# SCH_01_Power.net
KiCad netlist of a schematic drawn in Altium Designer
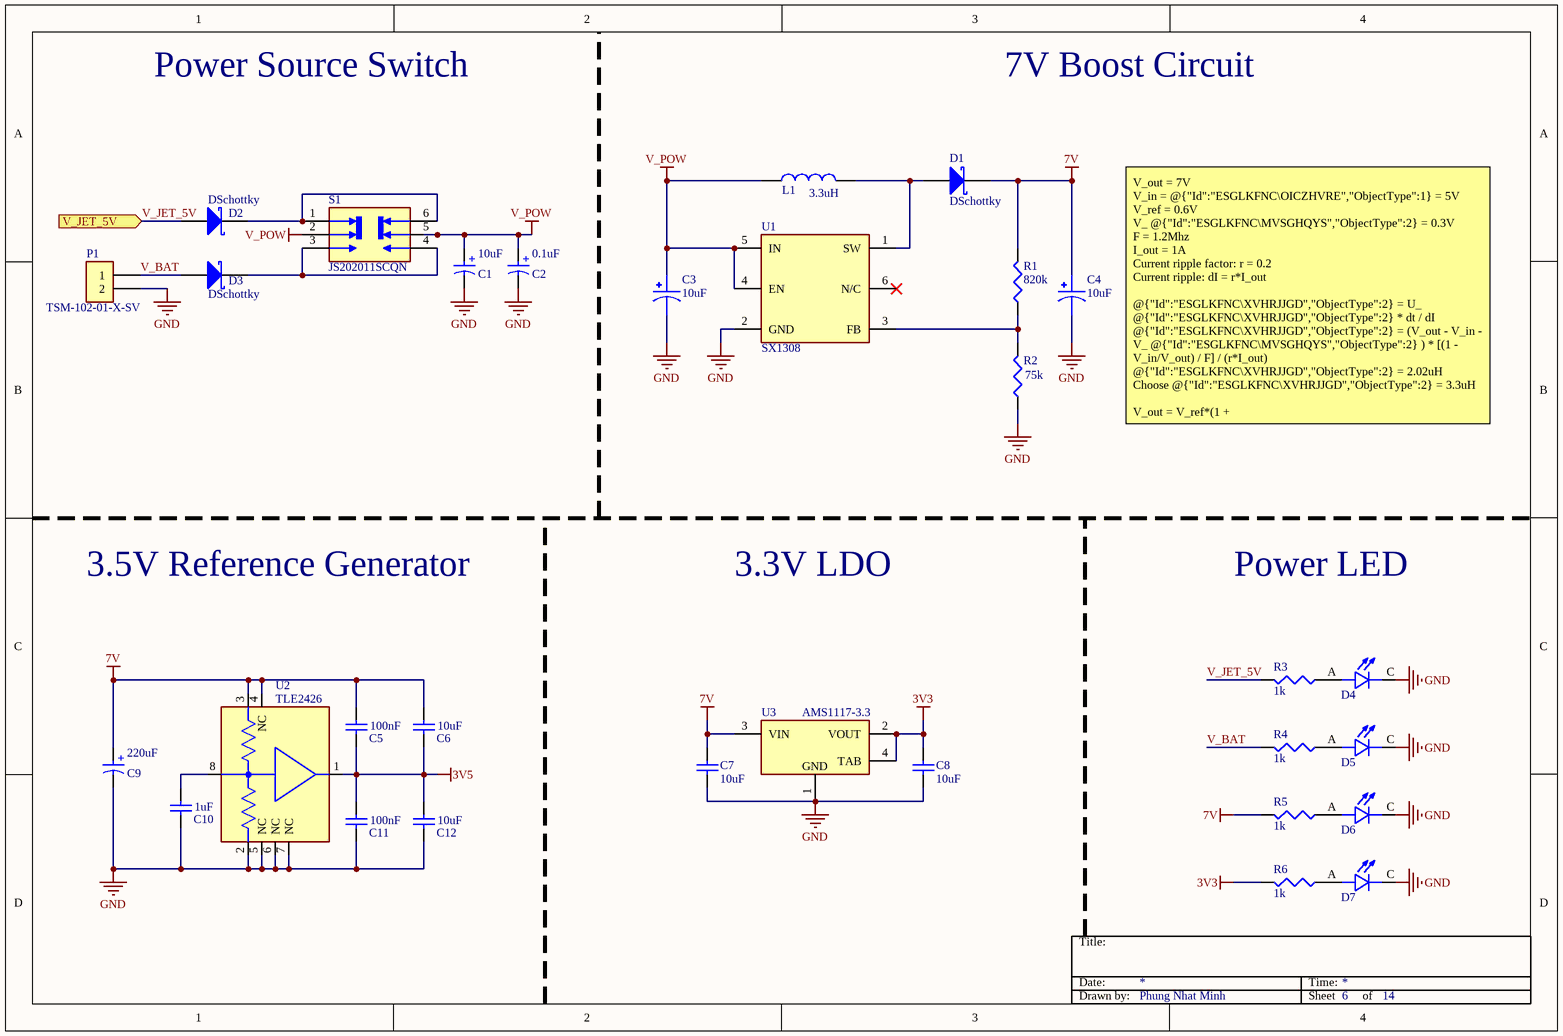
[diagram p0: SCH_01_Power.SchDoc]

(export (version "E")
  (design (tool "Eeschema 10.0.6"))
  (components
    (comp (ref "C1")
      (value "10uF")
      (footprint "WCAP-ASLI_D4H5.5")
      (description "WCAP-ASLI Aluminum Electrolytic Capacitor, V-Chip, D4 x H5.5mm, 10uF, 25V")
      (fields
        (field (name "MANUFACTURER PART NUMBER") "865080440002")
        (field (name "MANUFACTURER") "Wurth Elektronik")
      )
      (libsource (lib "Altium_WCAP-ASLI (rev22d)") (part "865080440002"))
    )
    (comp (ref "C2")
      (value "0.1uF")
      (footprint "WCAP-ASLI_D4H5.5")
      (description "WCAP-ASLI Aluminum Electrolytic Capacitor, V-Chip, D4 x H5.5mm, 0.1uF, 63V")
      (fields
        (field (name "MANUFACTURER PART NUMBER") "865080740002")
        (field (name "MANUFACTURER") "Wurth Elektronik")
      )
      (libsource (lib "Altium_WCAP-ASLI (rev22d)") (part "865080740002"))
    )
    (comp (ref "C3")
      (value "10uF")
      (footprint "CAPPM6032X280N")
      (description "10µF Molded Tantalum Capacitors 16V 2312 (6032 Metric) 2Ohm")
      (fields (field (name "MP") "TAJC106K016RNJ") (field (name "MF") "AVX Interconnect / Elco"))
      (libsource (lib "TAJC106K016RNJ") (part "TAJC106K016RNJ"))
    )
    (comp (ref "C4")
      (value "10uF")
      (footprint "CAPPM6032X280N")
      (description "10µF Molded Tantalum Capacitors 16V 2312 (6032 Metric) 2Ohm")
      (fields (field (name "MP") "TAJC106K016RNJ") (field (name "MF") "AVX Interconnect / Elco"))
      (libsource (lib "TAJC106K016RNJ") (part "TAJC106K016RNJ"))
    )
    (comp (ref "C5")
      (value "100nF")
      (footprint "WCAP-CSGP_0603_L1.6W0.8H0.8_Reflow")
      (description "WCAP-CSGP Multilayer Ceramic Chip Capacitor, General Purpose, size 0603, X7R, 100nF, 50VDC")
      (fields
        (field (name "MANUFACTURER PART NUMBER") "885012206095")
        (field (name "MANUFACTURER") "Wurth Elektronik")
      )
      (libsource (lib "Altium_WCAP-CSGP (rev24b)") (part "885012206095"))
    )
    (comp (ref "C6")
      (value "10uF")
      (footprint "WCAP-CSGP_0603_L1.6W0.8H0.8_Reflow")
      (description "WCAP-CSGP Multilayer Ceramic Chip Capacitor, General Purpose, size 0603, X5R, 10uF, 25VDC")
      (fields
        (field (name "MANUFACTURER PART NUMBER") "885012106031")
        (field (name "MANUFACTURER") "Wurth Elektronik")
      )
      (libsource (lib "Altium_WCAP-CSGP (rev24b)") (part "885012106031"))
    )
    (comp (ref "C7")
      (value "10uF")
      (footprint "WCAP-CSGP_0603_L1.6W0.8H0.8_Reflow")
      (description "WCAP-CSGP Multilayer Ceramic Chip Capacitor, General Purpose, size 0603, X5R, 10uF, 25VDC")
      (fields
        (field (name "MANUFACTURER PART NUMBER") "885012106031")
        (field (name "MANUFACTURER") "Wurth Elektronik")
      )
      (libsource (lib "Altium_WCAP-CSGP (rev24b)") (part "885012106031"))
    )
    (comp (ref "C8")
      (value "10uF")
      (footprint "WCAP-CSGP_0603_L1.6W0.8H0.8_Reflow")
      (description "WCAP-CSGP Multilayer Ceramic Chip Capacitor, General Purpose, size 0603, X5R, 10uF, 25VDC")
      (fields
        (field (name "MANUFACTURER PART NUMBER") "885012106031")
        (field (name "MANUFACTURER") "Wurth Elektronik")
      )
      (libsource (lib "Altium_WCAP-CSGP (rev24b)") (part "885012106031"))
    )
    (comp (ref "C9")
      (value "220uF")
      (footprint "WCAP-ASLI_D6.3H7.7")
      (description "WCAP-ASLI Aluminum Electrolytic Capacitor, V-Chip, D6.3 x H7.7mm, 220uF, 10V")
      (fields
        (field (name "MANUFACTURER PART NUMBER") "865080245009")
        (field (name "MANUFACTURER") "Wurth Elektronik")
      )
      (libsource (lib "Altium_WCAP-ASLI (rev22d)") (part "865080245009"))
    )
    (comp (ref "C10")
      (value "1uF")
      (footprint "WCAP-CSGP_0603_L1.6W0.8H0.8_Reflow")
      (description "WCAP-CSGP Multilayer Ceramic Chip Capacitor, General Purpose, size 0603, X7R, 1uF, 50VDC")
      (fields
        (field (name "MANUFACTURER PART NUMBER") "885012206126")
        (field (name "MANUFACTURER") "Wurth Elektronik")
      )
      (libsource (lib "Altium_WCAP-CSGP (rev24b)") (part "885012206126"))
    )
    (comp (ref "C11")
      (value "100nF")
      (footprint "WCAP-CSGP_0603_L1.6W0.8H0.8_Reflow")
      (description "WCAP-CSGP Multilayer Ceramic Chip Capacitor, General Purpose, size 0603, X7R, 100nF, 50VDC")
      (fields
        (field (name "MANUFACTURER PART NUMBER") "885012206095")
        (field (name "MANUFACTURER") "Wurth Elektronik")
      )
      (libsource (lib "Altium_WCAP-CSGP (rev24b)") (part "885012206095"))
    )
    (comp (ref "C12")
      (value "10uF")
      (footprint "WCAP-CSGP_0603_L1.6W0.8H0.8_Reflow")
      (description "WCAP-CSGP Multilayer Ceramic Chip Capacitor, General Purpose, size 0603, X5R, 10uF, 25VDC")
      (fields
        (field (name "MANUFACTURER PART NUMBER") "885012106031")
        (field (name "MANUFACTURER") "Wurth Elektronik")
      )
      (libsource (lib "Altium_WCAP-CSGP (rev24b)") (part "885012106031"))
    )
    (comp (ref "D1")
      (value "DSchottky")
      (footprint "PCBComponent_1")
      (libsource (lib "Diode_Schottky_SMA") (part "DSchottky"))
    )
    (comp (ref "D2")
      (value "DSchottky")
      (footprint "PCBComponent_1")
      (libsource (lib "Diode_Schottky_SMA") (part "DSchottky"))
    )
    (comp (ref "D3")
      (value "DSchottky")
      (footprint "PCBComponent_1")
      (libsource (lib "Diode_Schottky_SMA") (part "DSchottky"))
    )
    (comp (ref "D4")
      (value "SML-LXT0805IW-TR")
      (footprint "LEDC2012X120N")
      (fields (field (name "MF") "Lumex Opto/Components"))
      (libsource (lib "SML-LXT0805IW-TR") (part "SML-LXT0805IW-TR"))
    )
    (comp (ref "D5")
      (value "SML-LXT0805IW-TR")
      (footprint "LEDC2012X120N")
      (fields (field (name "MF") "Lumex Opto/Components"))
      (libsource (lib "SML-LXT0805IW-TR") (part "SML-LXT0805IW-TR"))
    )
    (comp (ref "D6")
      (value "SML-LXT0805IW-TR")
      (footprint "LEDC2012X120N")
      (fields (field (name "MF") "Lumex Opto/Components"))
      (libsource (lib "SML-LXT0805IW-TR") (part "SML-LXT0805IW-TR"))
    )
    (comp (ref "D7")
      (value "SML-LXT0805IW-TR")
      (footprint "LEDC2012X120N")
      (fields (field (name "MF") "Lumex Opto/Components"))
      (libsource (lib "SML-LXT0805IW-TR") (part "SML-LXT0805IW-TR"))
    )
    (comp (ref "L1")
      (value "3.3uH")
      (footprint "WE-PD2A_4532")
      (description "WE-PD2A SMT Power Inductor, size 4532, 3.3µH, 2A, 3.3Ω")
      (fields
        (field (name "MANUFACTURER PART NUMBER") "784773147")
        (field (name "MANUFACTURER") "Wurth Elektronik")
      )
      (libsource (lib "Altium_WE-PD2A (rev22c)") (part "784773147"))
    )
    (comp (ref "P1")
      (value "TSM-102-01-X-SV")
      (footprint "SAMTEC_TSM-102-01-X-SV")
      (description "TSM - Samtec 2.54mm Single Row Vertical Surface Mount Header 5.84mm Post Height (01) - Fast Stock")
      (fields (field (name "MF") "Samtec") (field (name "MP") "TSM-102-01-L-SV"))
      (libsource (lib "TSM-102-01-X-SV") (part "TSM-102-01-X-SV"))
    )
    (comp (ref "R1")
      (value "820k")
      (footprint "WRIS-PSMB_0603_L1.6W0.8H0.35")
      (description "WRIS-PSMB Metal Plate Resistor, SMT, size 0603, 0.33W, 5mΩ, +/-1%")
      (fields
        (field (name "MANUFACTURER PART NUMBER") "580060716001")
        (field (name "MANUFACTURER") "Wurth Elektronik")
      )
      (libsource (lib "Altium_WRIS-PSMB (rev22a)") (part "580060716001"))
    )
    (comp (ref "R2")
      (value "75k")
      (footprint "WRIS-PSMB_0603_L1.6W0.8H0.35")
      (description "WRIS-PSMB Metal Plate Resistor, SMT, size 0603, 0.33W, 5mΩ, +/-1%")
      (fields
        (field (name "MANUFACTURER PART NUMBER") "580060716001")
        (field (name "MANUFACTURER") "Wurth Elektronik")
      )
      (libsource (lib "Altium_WRIS-PSMB (rev22a)") (part "580060716001"))
    )
    (comp (ref "R3")
      (value "1k")
      (footprint "WRIS-PSMB_0603_L1.6W0.8H0.35")
      (description "WRIS-PSMB Metal Plate Resistor, SMT, size 0603, 0.33W, 5mΩ, +/-1%")
      (fields
        (field (name "MANUFACTURER PART NUMBER") "580060716001")
        (field (name "MANUFACTURER") "Wurth Elektronik")
      )
      (libsource (lib "Altium_WRIS-PSMB (rev22a)") (part "580060716001"))
    )
    (comp (ref "R4")
      (value "1k")
      (footprint "WRIS-PSMB_0603_L1.6W0.8H0.35")
      (description "WRIS-PSMB Metal Plate Resistor, SMT, size 0603, 0.33W, 5mΩ, +/-1%")
      (fields
        (field (name "MANUFACTURER PART NUMBER") "580060716001")
        (field (name "MANUFACTURER") "Wurth Elektronik")
      )
      (libsource (lib "Altium_WRIS-PSMB (rev22a)") (part "580060716001"))
    )
    (comp (ref "R5")
      (value "1k")
      (footprint "WRIS-PSMB_0603_L1.6W0.8H0.35")
      (description "WRIS-PSMB Metal Plate Resistor, SMT, size 0603, 0.33W, 5mΩ, +/-1%")
      (fields
        (field (name "MANUFACTURER PART NUMBER") "580060716001")
        (field (name "MANUFACTURER") "Wurth Elektronik")
      )
      (libsource (lib "Altium_WRIS-PSMB (rev22a)") (part "580060716001"))
    )
    (comp (ref "R6")
      (value "1k")
      (footprint "WRIS-PSMB_0603_L1.6W0.8H0.35")
      (description "WRIS-PSMB Metal Plate Resistor, SMT, size 0603, 0.33W, 5mΩ, +/-1%")
      (fields
        (field (name "MANUFACTURER PART NUMBER") "580060716001")
        (field (name "MANUFACTURER") "Wurth Elektronik")
      )
      (libsource (lib "Altium_WRIS-PSMB (rev22a)") (part "580060716001"))
    )
    (comp (ref "S1")
      (value "JS202011SCQN")
      (footprint "SW_JS202011SCQN")
      (libsource (lib "JS202011SCQN") (part "JS202011SCQN"))
    )
    (comp (ref "U1")
      (value "SX1308")
      (footprint "SOT-23-6")
      (description "SX1308 - Transceiver; LoRaÂ® Evaluation Board")
      (fields (field (name "MF") "Semtech Corporation"))
      (libsource (lib "SX1308") (part "SX1308"))
    )
    (comp (ref "U2")
      (value "TLE2426")
      (footprint "SO8")
      (description "Ground Reference (Virtual) Voltage Reference IC Adjustable 2V 20 VV Â±1% 20 mA 8-PDIP")
      (fields (field (name "MF") "Texas Instruments"))
      (libsource (lib "TLE2426") (part "TLE2426"))
    )
    (comp (ref "U3")
      (value "AMS1117-3.3")
      (footprint "SOT229P700X180-4N")
      (description "1A LOW DROPOUT VOLTAGE REGULATOR")
      (fields (field (name "MP") "AMS1117-5.0") (field (name "MF") "ams"))
      (libsource (lib "AMS1117-5.0") (part "AMS1117-5.0"))
    )
  )
  (nets
    (net (code "1") (name "/V_BAT") (class "Default")
      (node (ref "D3") (pin "1") (pinfunction "A_1") (pintype "passive"))
      (node (ref "P1") (pin "1") (pinfunction "1_1") (pintype "passive"))
      (node (ref "R4") (pin "2") (pinfunction "2_2") (pintype "passive"))
    )
    (net (code "2") (name "/V_JET_5V") (class "Default")
      (node (ref "D2") (pin "1") (pinfunction "A_1") (pintype "passive"))
      (node (ref "R3") (pin "2") (pinfunction "2_2") (pintype "passive"))
    )
    (net (code "3") (name "3V3") (class "Default")
      (node (ref "C8") (pin "2") (pinfunction "2_2") (pintype "passive"))
      (node (ref "R6") (pin "2") (pinfunction "2_2") (pintype "passive"))
      (node (ref "U3") (pin "2") (pinfunction "VOUT_2") (pintype "power_in"))
      (node (ref "U3") (pin "4") (pinfunction "TAB_4") (pintype "power_in"))
    )
    (net (code "4") (name "3V5") (class "Default")
      (node (ref "C11") (pin "2") (pinfunction "2_2") (pintype "passive"))
      (node (ref "C12") (pin "2") (pinfunction "2_2") (pintype "passive"))
      (node (ref "C5") (pin "1") (pinfunction "1_1") (pintype "passive"))
      (node (ref "C6") (pin "1") (pinfunction "1_1") (pintype "passive"))
      (node (ref "U2") (pin "1") (pinfunction "OUT_1") (pintype "passive"))
    )
    (net (code "5") (name "7V") (class "Default")
      (node (ref "C4") (pin "1") (pinfunction "1_1") (pintype "passive"))
      (node (ref "C5") (pin "2") (pinfunction "2_2") (pintype "passive"))
      (node (ref "C6") (pin "2") (pinfunction "2_2") (pintype "passive"))
      (node (ref "C7") (pin "2") (pinfunction "2_2") (pintype "passive"))
      (node (ref "C9") (pin "1") (pinfunction "P_1") (pintype "passive"))
      (node (ref "D1") (pin "2") (pinfunction "K_2") (pintype "passive"))
      (node (ref "R1") (pin "2") (pinfunction "2_2") (pintype "passive"))
      (node (ref "R5") (pin "2") (pinfunction "2_2") (pintype "passive"))
      (node (ref "U2") (pin "3") (pinfunction "V+_3") (pintype "power_in"))
      (node (ref "U2") (pin "4") (pinfunction "NC_4") (pintype "passive"))
      (node (ref "U3") (pin "3") (pinfunction "VIN_3") (pintype "power_in"))
    )
    (net (code "6") (name "GND") (class "Default")
      (node (ref "C1") (pin "2") (pinfunction "N_2") (pintype "passive"))
      (node (ref "C10") (pin "1") (pinfunction "1_1") (pintype "passive"))
      (node (ref "C11") (pin "1") (pinfunction "1_1") (pintype "passive"))
      (node (ref "C12") (pin "1") (pinfunction "1_1") (pintype "passive"))
      (node (ref "C2") (pin "2") (pinfunction "N_2") (pintype "passive"))
      (node (ref "C3") (pin "2") (pinfunction "2_2") (pintype "passive"))
      (node (ref "C4") (pin "2") (pinfunction "2_2") (pintype "passive"))
      (node (ref "C7") (pin "1") (pinfunction "1_1") (pintype "passive"))
      (node (ref "C8") (pin "1") (pinfunction "1_1") (pintype "passive"))
      (node (ref "C9") (pin "2") (pinfunction "N_2") (pintype "passive"))
      (node (ref "D4") (pin "C") (pinfunction "C_C") (pintype "passive"))
      (node (ref "D5") (pin "C") (pinfunction "C_C") (pintype "passive"))
      (node (ref "D6") (pin "C") (pinfunction "C_C") (pintype "passive"))
      (node (ref "D7") (pin "C") (pinfunction "C_C") (pintype "passive"))
      (node (ref "P1") (pin "2") (pinfunction "2_2") (pintype "passive"))
      (node (ref "R2") (pin "1") (pinfunction "1_1") (pintype "passive"))
      (node (ref "U1") (pin "2") (pinfunction "GND_2") (pintype "power_in"))
      (node (ref "U2") (pin "2") (pinfunction "V-_2") (pintype "power_in"))
      (node (ref "U2") (pin "5") (pinfunction "NC_5") (pintype "passive"))
      (node (ref "U2") (pin "6") (pinfunction "NC_6") (pintype "passive"))
      (node (ref "U2") (pin "7") (pinfunction "NC_7") (pintype "passive"))
      (node (ref "U3") (pin "1") (pinfunction "GND/ADJ_1") (pintype "power_in"))
    )
    (net (code "7") (name "Net-(D1-A)") (class "Default")
      (node (ref "D1") (pin "1") (pinfunction "A_1") (pintype "passive"))
      (node (ref "L1") (pin "2") (pinfunction "2_2") (pintype "passive"))
      (node (ref "U1") (pin "1") (pinfunction "SW_1") (pintype "power_in"))
    )
    (net (code "8") (name "Net-(D2-K)") (class "Default")
      (node (ref "D2") (pin "2") (pinfunction "K_2") (pintype "passive"))
      (node (ref "S1") (pin "1") (pinfunction "1_1") (pintype "passive"))
      (node (ref "S1") (pin "6") (pinfunction "6_6") (pintype "passive"))
    )
    (net (code "9") (name "Net-(D3-K)") (class "Default")
      (node (ref "D3") (pin "2") (pinfunction "K_2") (pintype "passive"))
      (node (ref "S1") (pin "3") (pinfunction "3_3") (pintype "passive"))
      (node (ref "S1") (pin "4") (pinfunction "4_4") (pintype "passive"))
    )
    (net (code "10") (name "Net-(D4-PadA)") (class "Default")
      (node (ref "D4") (pin "A") (pinfunction "A_A") (pintype "passive"))
      (node (ref "R3") (pin "1") (pinfunction "1_1") (pintype "passive"))
    )
    (net (code "11") (name "Net-(D5-PadA)") (class "Default")
      (node (ref "D5") (pin "A") (pinfunction "A_A") (pintype "passive"))
      (node (ref "R4") (pin "1") (pinfunction "1_1") (pintype "passive"))
    )
    (net (code "12") (name "Net-(D6-PadA)") (class "Default")
      (node (ref "D6") (pin "A") (pinfunction "A_A") (pintype "passive"))
      (node (ref "R5") (pin "1") (pinfunction "1_1") (pintype "passive"))
    )
    (net (code "13") (name "Net-(D7-PadA)") (class "Default")
      (node (ref "D7") (pin "A") (pinfunction "A_A") (pintype "passive"))
      (node (ref "R6") (pin "1") (pinfunction "1_1") (pintype "passive"))
    )
    (net (code "14") (name "Net-(U1-FB)") (class "Default")
      (node (ref "R1") (pin "1") (pinfunction "1_1") (pintype "passive"))
      (node (ref "R2") (pin "2") (pinfunction "2_2") (pintype "passive"))
      (node (ref "U1") (pin "3") (pinfunction "FB_3") (pintype "power_in"))
    )
    (net (code "15") (name "Net-(U2-NR)") (class "Default")
      (node (ref "C10") (pin "2") (pinfunction "2_2") (pintype "passive"))
      (node (ref "U2") (pin "8") (pinfunction "NR_8") (pintype "passive"))
    )
    (net (code "16") (name "V_POW") (class "Default")
      (node (ref "C1") (pin "1") (pinfunction "P_1") (pintype "passive"))
      (node (ref "C2") (pin "1") (pinfunction "P_1") (pintype "passive"))
      (node (ref "C3") (pin "1") (pinfunction "1_1") (pintype "passive"))
      (node (ref "L1") (pin "1") (pinfunction "1_1") (pintype "passive"))
      (node (ref "S1") (pin "2") (pinfunction "2_2") (pintype "passive"))
      (node (ref "S1") (pin "5") (pinfunction "5_5") (pintype "passive"))
      (node (ref "U1") (pin "4") (pinfunction "EN_4") (pintype "power_in"))
      (node (ref "U1") (pin "5") (pinfunction "IN_5") (pintype "power_in"))
    )
    (net (code "17") (name "unconnected-(U1-N{slash}C-Pad6)") (class "Default")
      (node (ref "U1") (pin "6") (pinfunction "N/C_6") (pintype "power_in+no_connect"))
    )
  )
)
